# mother.net
KiCad netlist of a schematic drawn in EAGLE
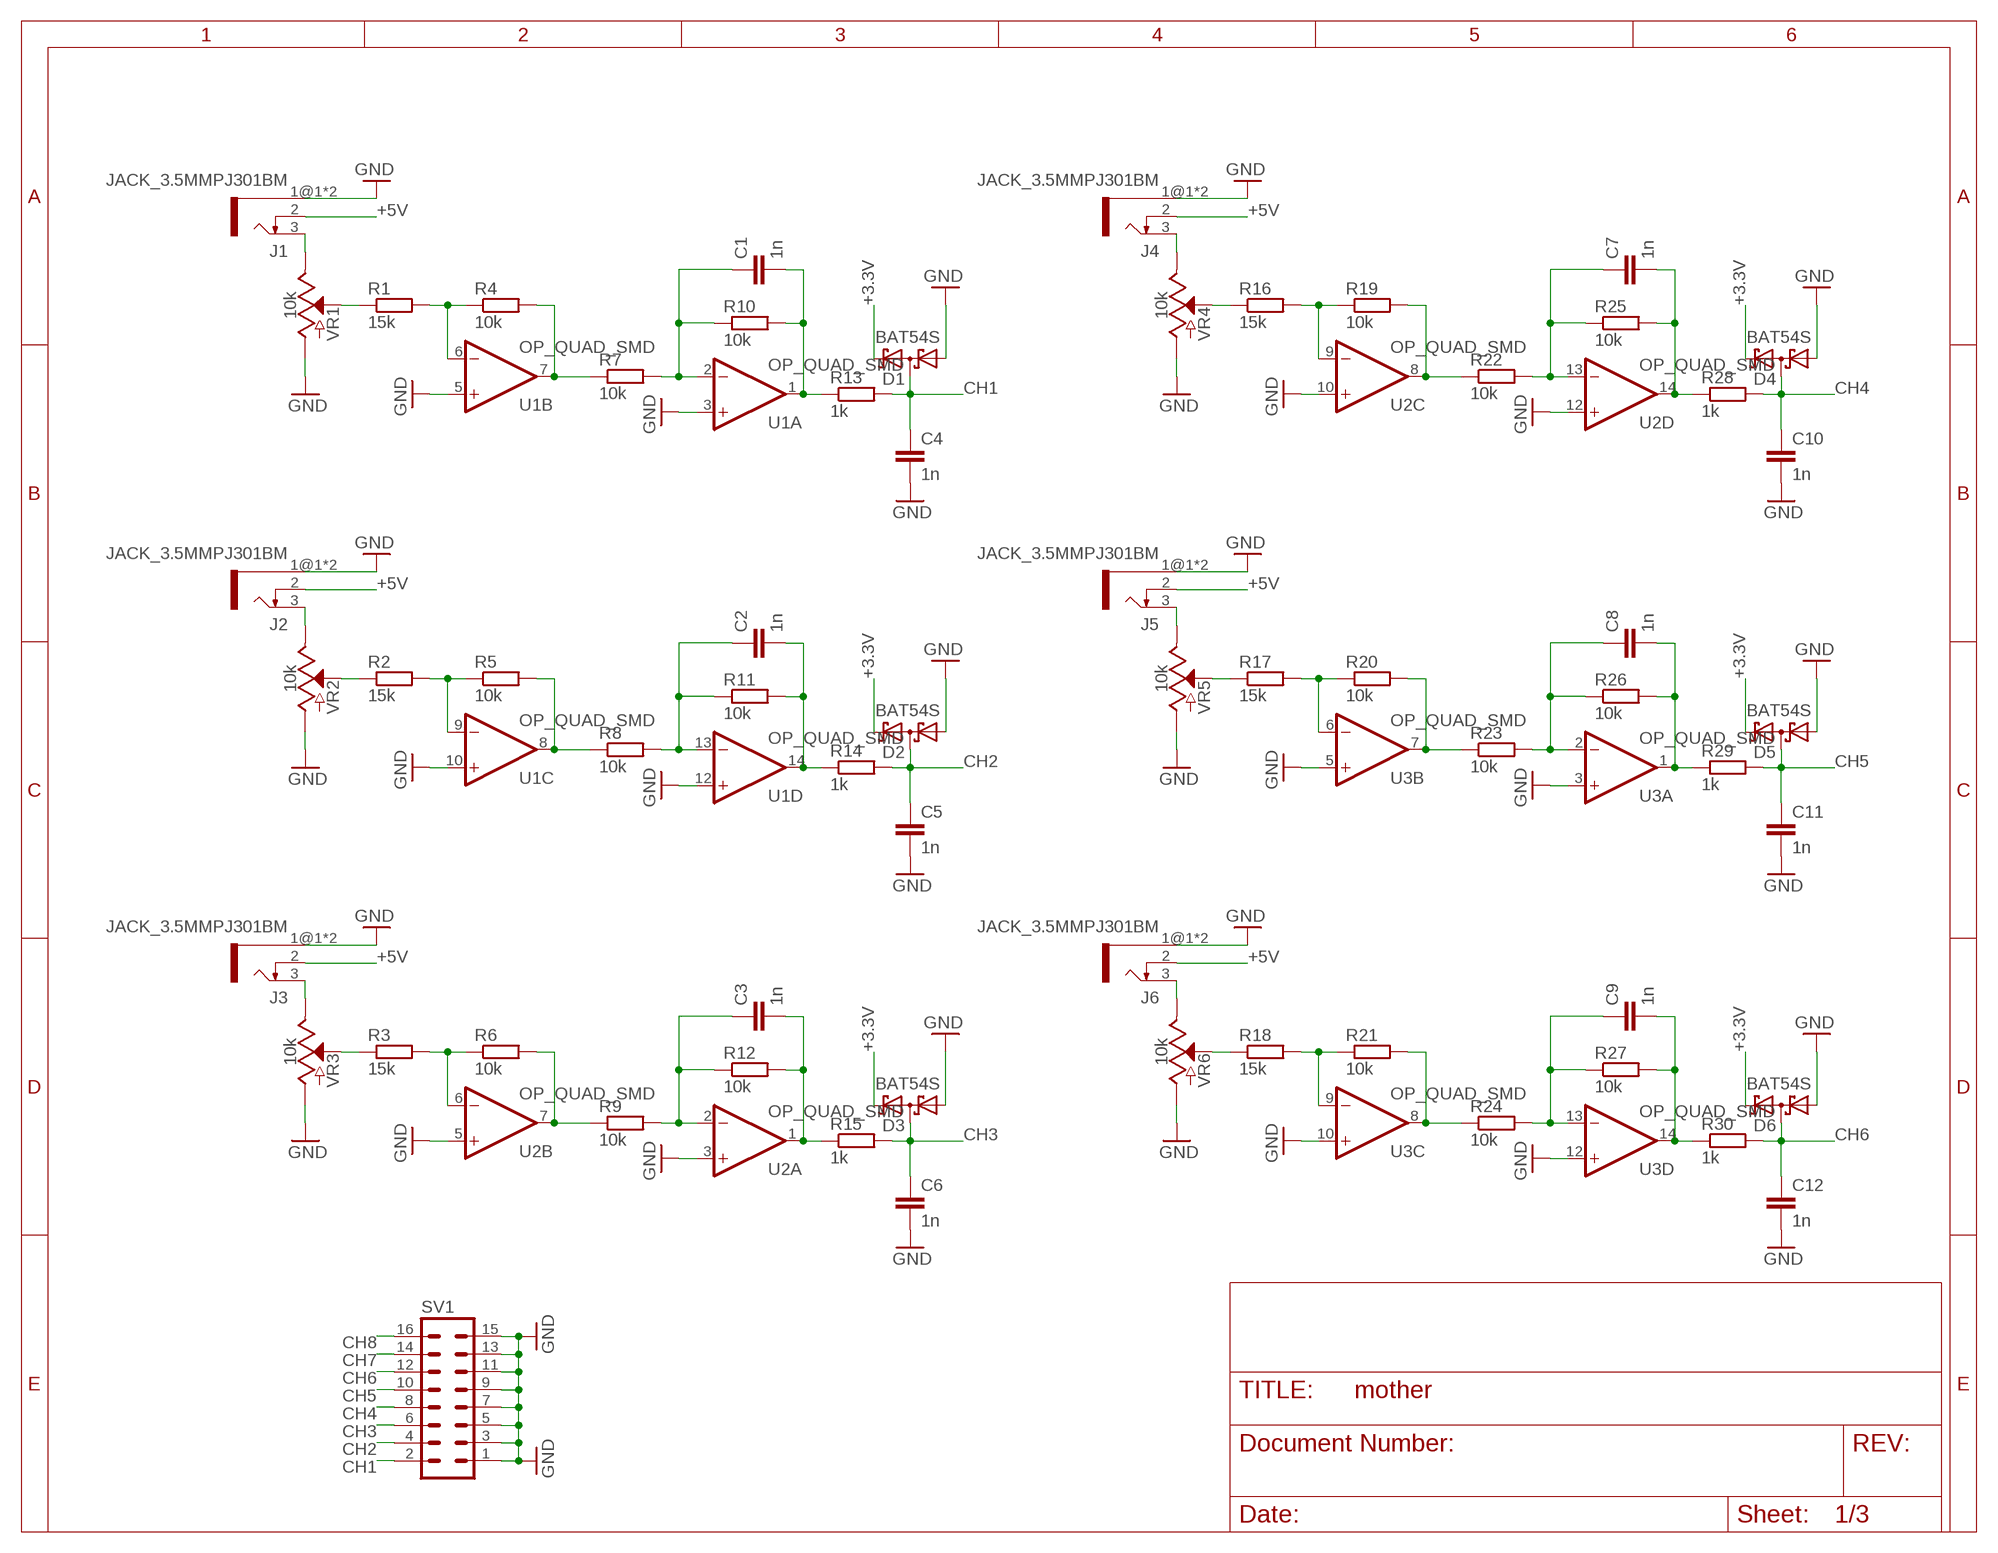
[diagram p0: schematic, sheet 1]
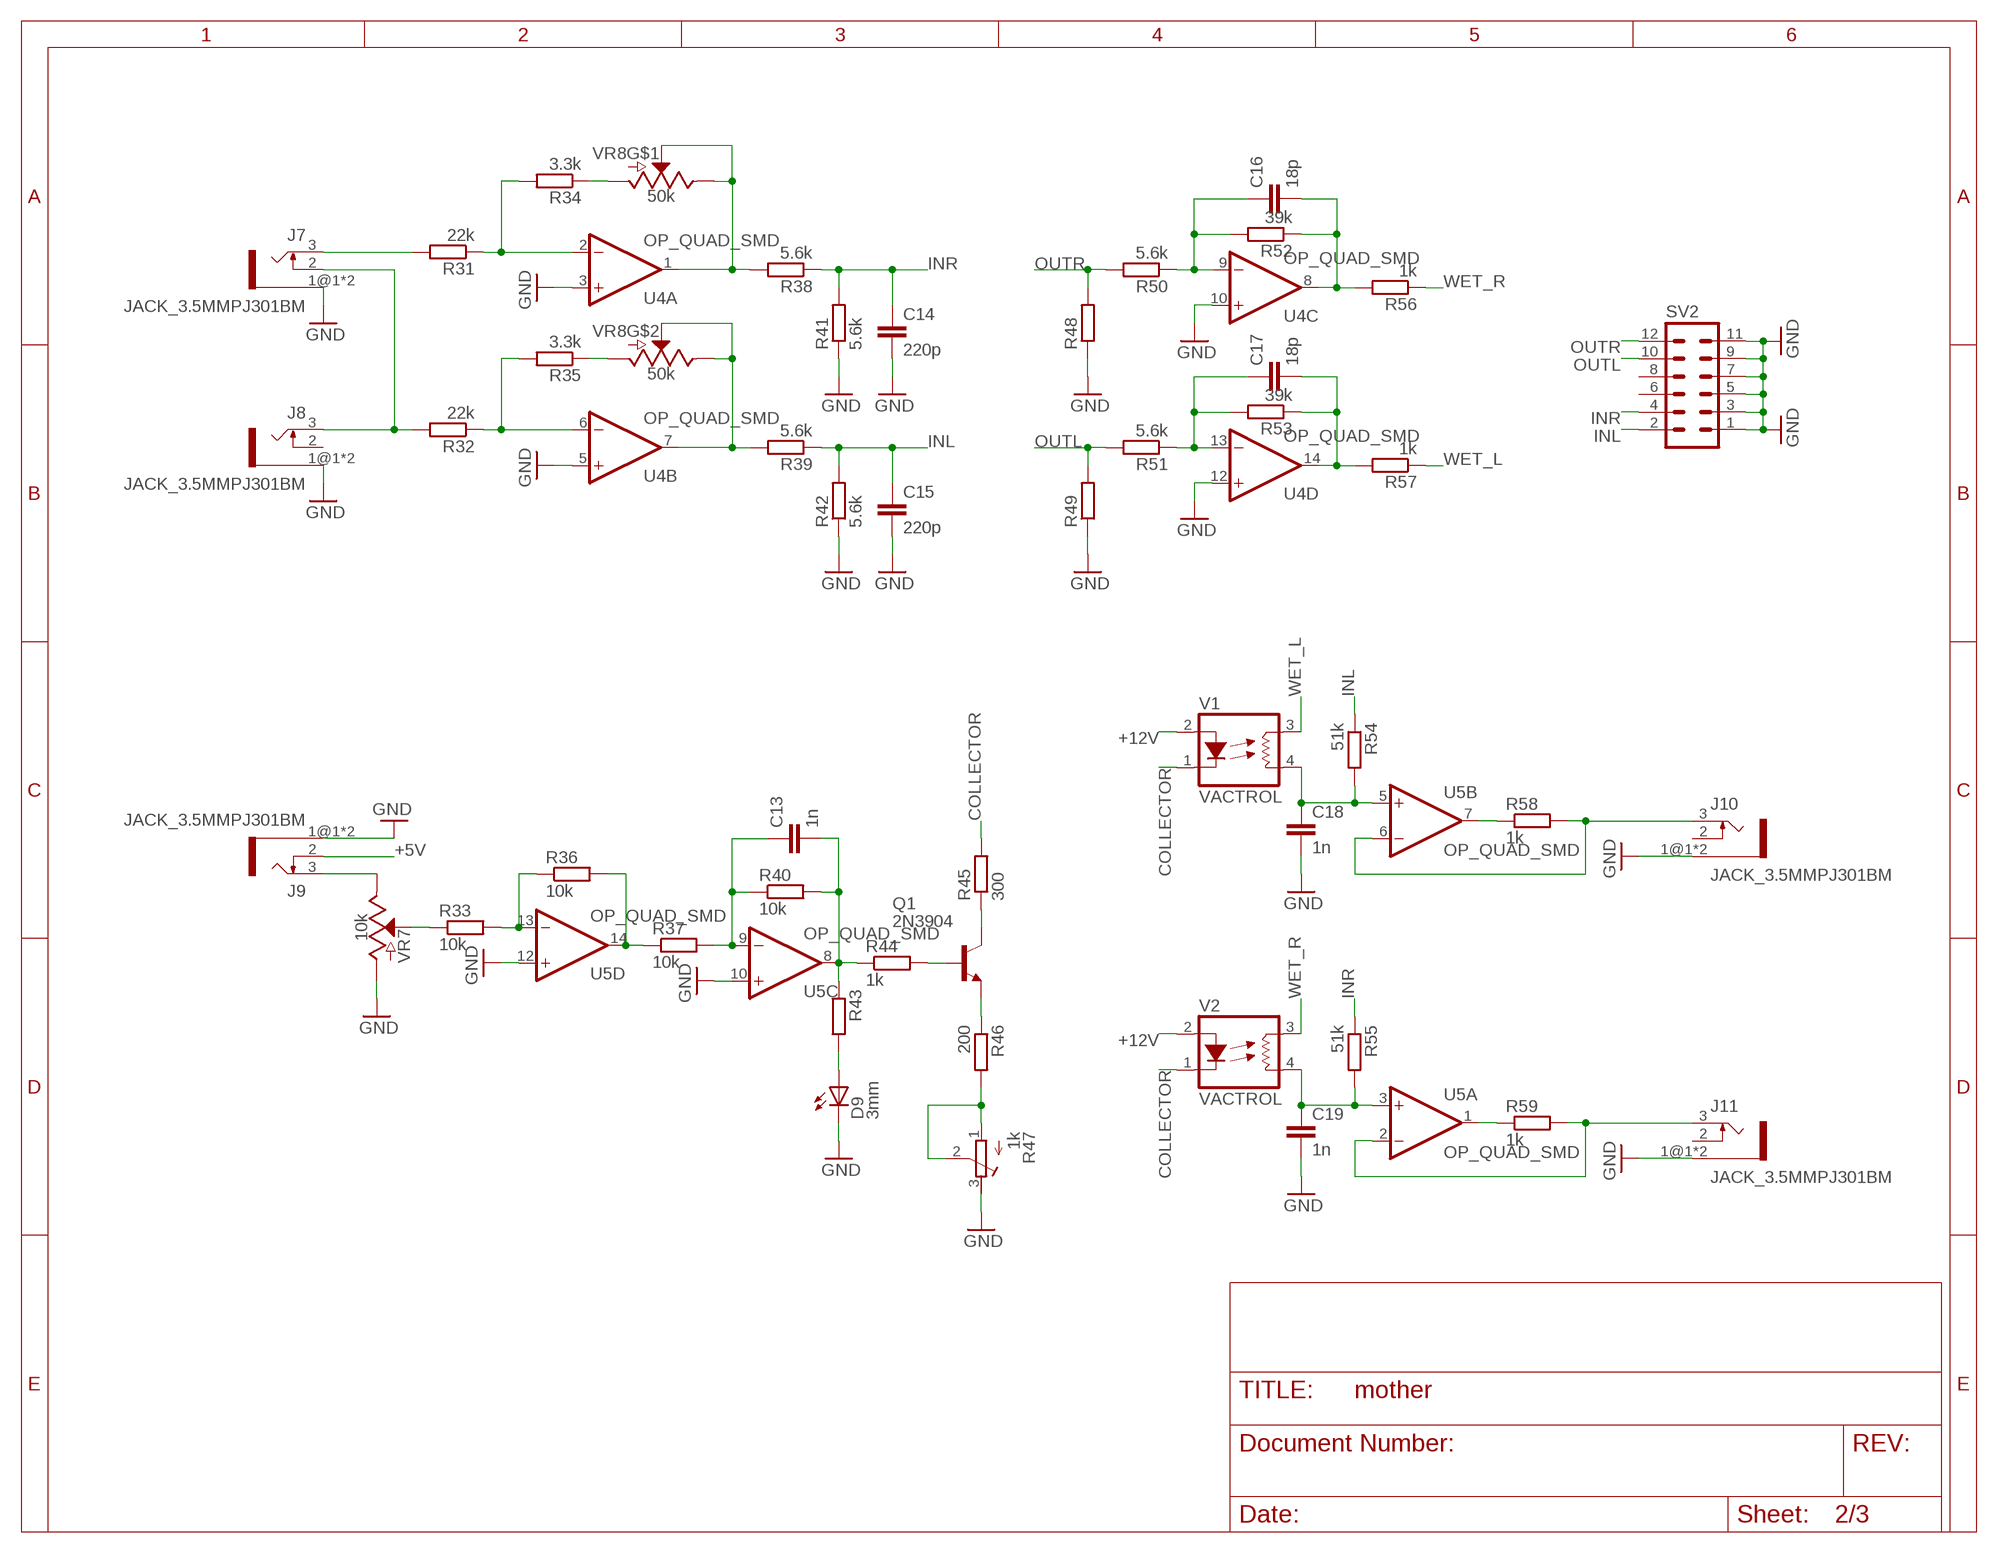
[diagram p1: schematic, sheet 2]
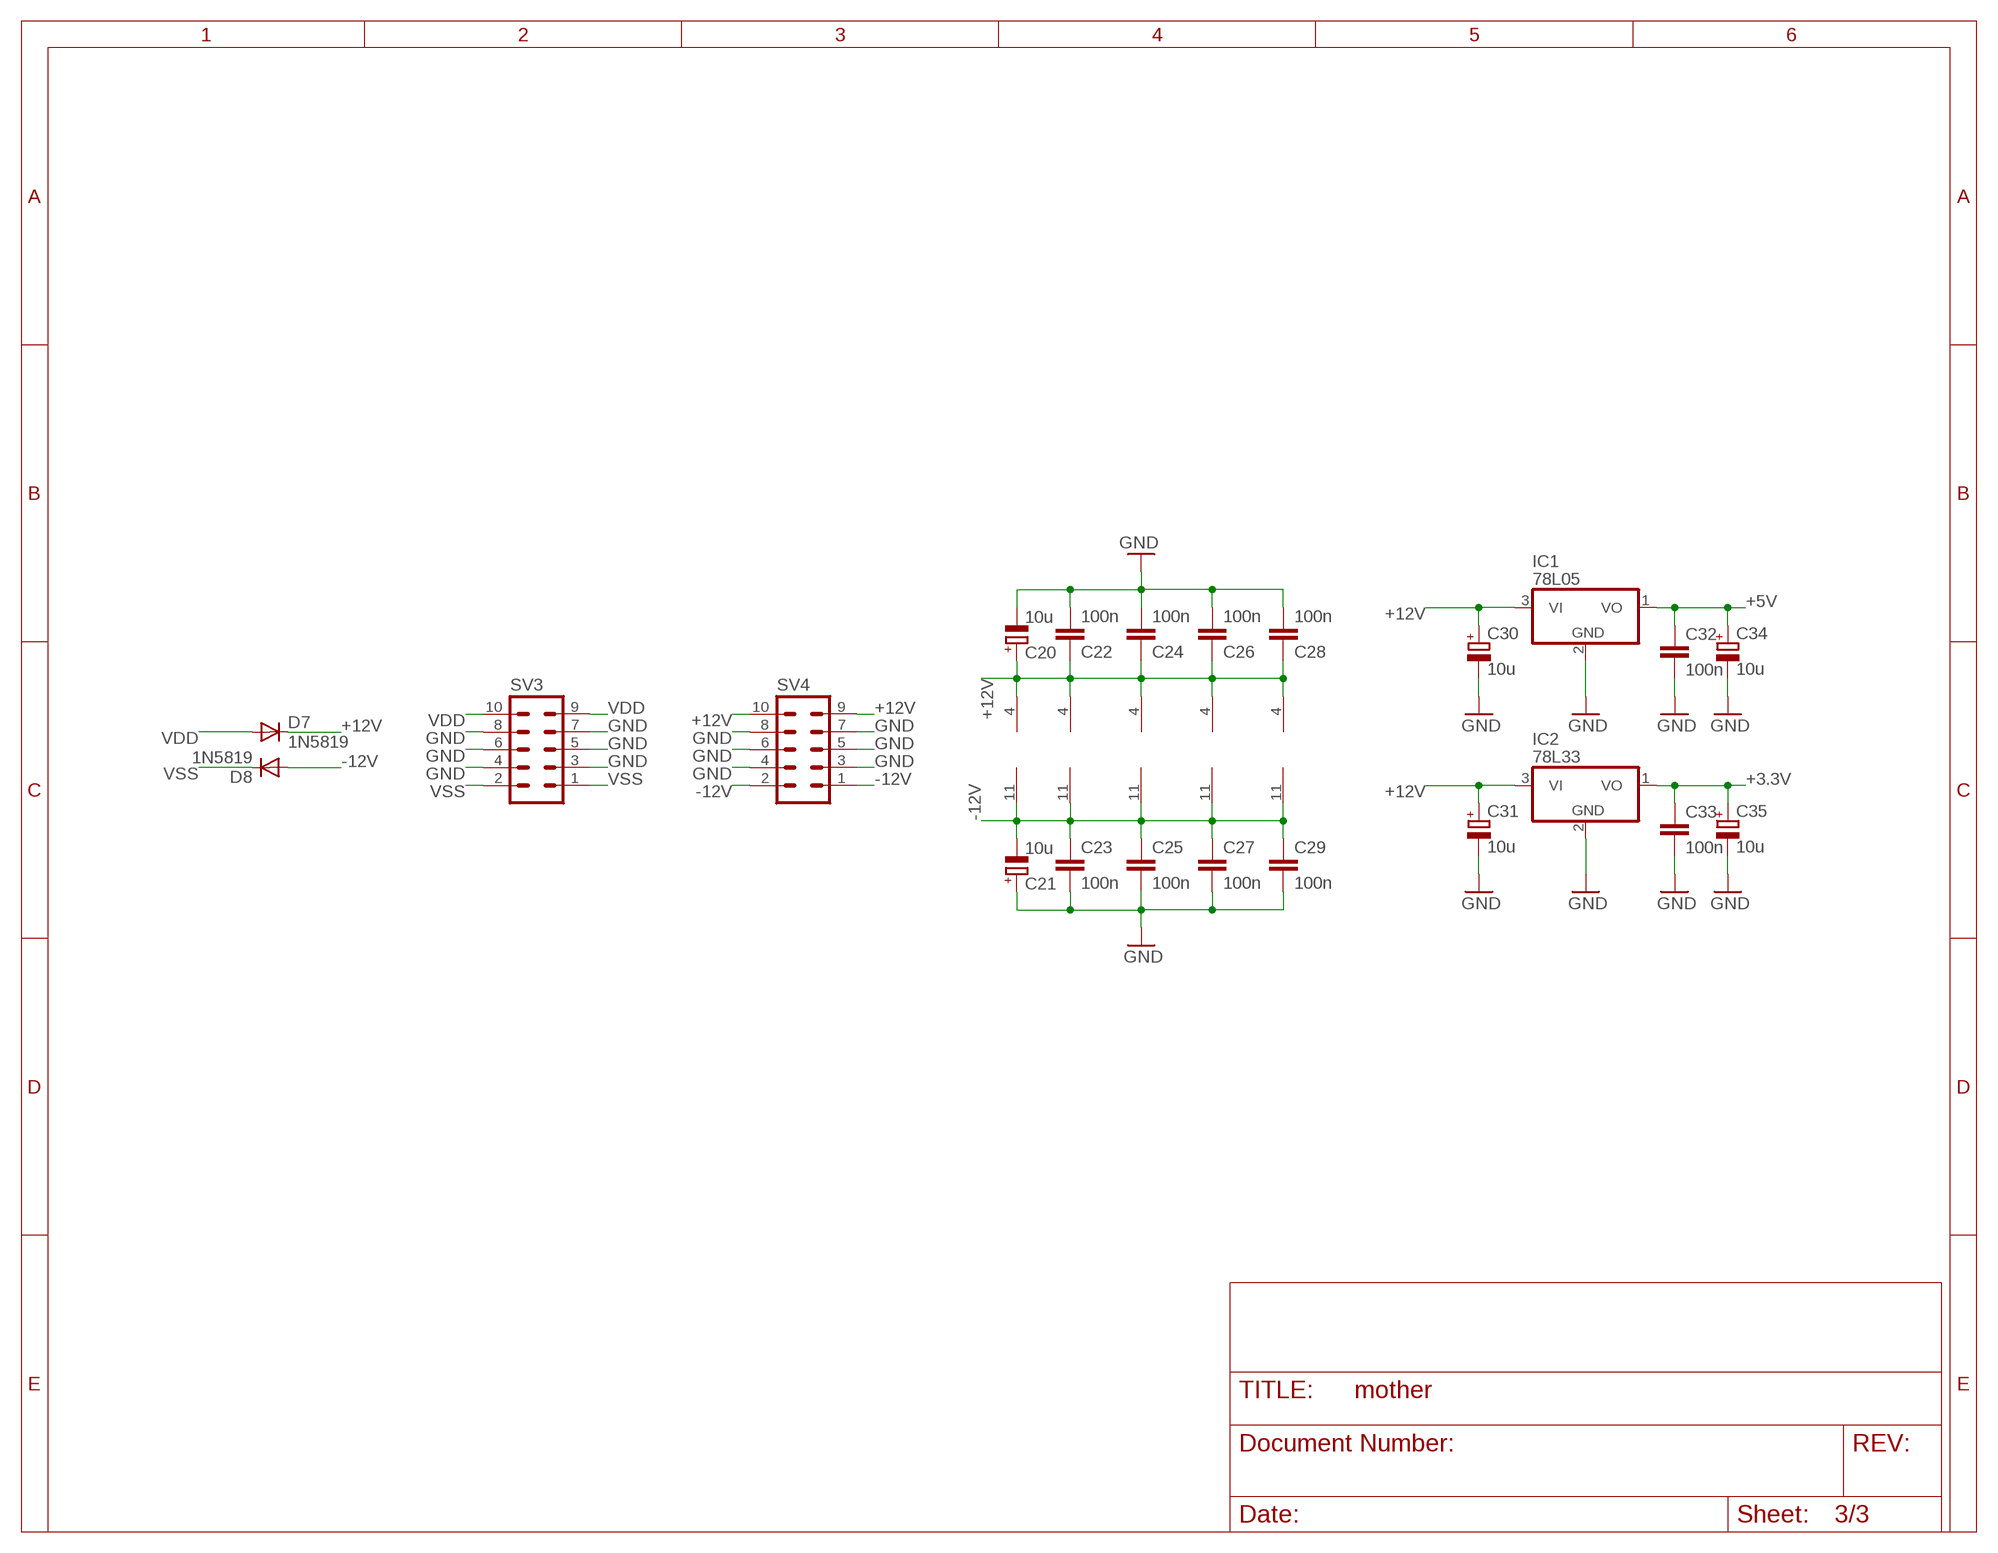
[diagram p2: schematic, sheet 3]

(export (version "E")
  (design (tool "Eeschema 10.0.6"))
  (components
    (comp (ref "C20")
      (value "10u")
      (footprint "eagle-import:E2,5-6")
      (libsource (lib "eagle-import") (part "CPOL-EUE2.5-6"))
    )
    (comp (ref "C21")
      (value "10u")
      (footprint "eagle-import:E2,5-6")
      (libsource (lib "eagle-import") (part "CPOL-EUE2.5-6"))
    )
    (comp (ref "C22")
      (value "100n")
      (footprint "eagle-import:C5B3.5")
      (libsource (lib "eagle-import") (part "C5/3.5"))
    )
    (comp (ref "C23")
      (value "100n")
      (footprint "eagle-import:C5B3.5")
      (libsource (lib "eagle-import") (part "C5/3.5"))
    )
    (comp (ref "C24")
      (value "100n")
      (footprint "eagle-import:C5B3.5")
      (libsource (lib "eagle-import") (part "C5/3.5"))
    )
    (comp (ref "C25")
      (value "100n")
      (footprint "eagle-import:C5B3.5")
      (libsource (lib "eagle-import") (part "C5/3.5"))
    )
    (comp (ref "C26")
      (value "100n")
      (footprint "eagle-import:C5B3.5")
      (libsource (lib "eagle-import") (part "C5/3.5"))
    )
    (comp (ref "C27")
      (value "100n")
      (footprint "eagle-import:C5B3.5")
      (libsource (lib "eagle-import") (part "C5/3.5"))
    )
    (comp (ref "C28")
      (value "100n")
      (footprint "eagle-import:C5B3.5")
      (libsource (lib "eagle-import") (part "C5/3.5"))
    )
    (comp (ref "C29")
      (value "100n")
      (footprint "eagle-import:C5B3.5")
      (libsource (lib "eagle-import") (part "C5/3.5"))
    )
    (comp (ref "C30")
      (value "10u")
      (footprint "eagle-import:E2,5-6")
      (libsource (lib "eagle-import") (part "CPOL-EUE2.5-6"))
    )
    (comp (ref "C31")
      (value "10u")
      (footprint "eagle-import:E2,5-6")
      (libsource (lib "eagle-import") (part "CPOL-EUE2.5-6"))
    )
    (comp (ref "C32")
      (value "100n")
      (footprint "eagle-import:C5B3.5")
      (libsource (lib "eagle-import") (part "C5/3.5"))
    )
    (comp (ref "C33")
      (value "100n")
      (footprint "eagle-import:C5B3.5")
      (libsource (lib "eagle-import") (part "C5/3.5"))
    )
    (comp (ref "C34")
      (value "10u")
      (footprint "eagle-import:E2,5-6")
      (libsource (lib "eagle-import") (part "CPOL-EUE2.5-6"))
    )
    (comp (ref "C35")
      (value "10u")
      (footprint "eagle-import:E2,5-6")
      (libsource (lib "eagle-import") (part "CPOL-EUE2.5-6"))
    )
    (comp (ref "D7")
      (value "1N5819")
      (footprint "eagle-import:SOD-123_MINI-SMA")
      (libsource (lib "eagle-import") (part "CGRM400-G1"))
    )
    (comp (ref "D8")
      (value "1N5819")
      (footprint "eagle-import:SOD-123_MINI-SMA")
      (libsource (lib "eagle-import") (part "CGRM400-G1"))
    )
    (comp (ref "IC1")
      (value "78L05")
      (footprint "eagle-import:TO92")
      (libsource (lib "eagle-import") (part "78ZL05"))
    )
    (comp (ref "IC2")
      (value "78L33")
      (footprint "eagle-import:TO92")
      (libsource (lib "eagle-import") (part "78ZL05"))
    )
    (comp (ref "SV3")
      (value "MA05-2")
      (footprint "eagle-import:MA05-2")
      (libsource (lib "eagle-import") (part "MA05-2"))
    )
    (comp (ref "SV4")
      (value "MA05-2")
      (footprint "eagle-import:MA05-2")
      (libsource (lib "eagle-import") (part "MA05-2"))
    )
    (comp (ref "U1")
      (value "OP_QUAD_SMD")
      (footprint "eagle-import:SO14")
      (libsource (lib "eagle-import") (part "OP_QUAD_SMD"))
    )
    (comp (ref "U2")
      (value "OP_QUAD_SMD")
      (footprint "eagle-import:SO14")
      (libsource (lib "eagle-import") (part "OP_QUAD_SMD"))
    )
    (comp (ref "U3")
      (value "OP_QUAD_SMD")
      (footprint "eagle-import:SO14")
      (libsource (lib "eagle-import") (part "OP_QUAD_SMD"))
    )
    (comp (ref "U4")
      (value "OP_QUAD_SMD")
      (footprint "eagle-import:SO14")
      (libsource (lib "eagle-import") (part "OP_QUAD_SMD"))
    )
    (comp (ref "U5")
      (value "OP_QUAD_SMD")
      (footprint "eagle-import:SO14")
      (libsource (lib "eagle-import") (part "OP_QUAD_SMD"))
    )
    (comp (ref "C1")
      (value "1n")
      (footprint "eagle-import:C0603")
      (libsource (lib "eagle-import") (part "CC0603"))
    )
    (comp (ref "C2")
      (value "1n")
      (footprint "eagle-import:C0603")
      (libsource (lib "eagle-import") (part "CC0603"))
    )
    (comp (ref "C3")
      (value "1n")
      (footprint "eagle-import:C0603")
      (libsource (lib "eagle-import") (part "CC0603"))
    )
    (comp (ref "C4")
      (value "1n")
      (footprint "eagle-import:C0603")
      (libsource (lib "eagle-import") (part "CC0603"))
    )
    (comp (ref "C5")
      (value "1n")
      (footprint "eagle-import:C0603")
      (libsource (lib "eagle-import") (part "CC0603"))
    )
    (comp (ref "C6")
      (value "1n")
      (footprint "eagle-import:C0603")
      (libsource (lib "eagle-import") (part "CC0603"))
    )
    (comp (ref "C7")
      (value "1n")
      (footprint "eagle-import:C0603")
      (libsource (lib "eagle-import") (part "CC0603"))
    )
    (comp (ref "C8")
      (value "1n")
      (footprint "eagle-import:C0603")
      (libsource (lib "eagle-import") (part "CC0603"))
    )
    (comp (ref "C9")
      (value "1n")
      (footprint "eagle-import:C0603")
      (libsource (lib "eagle-import") (part "CC0603"))
    )
    (comp (ref "C10")
      (value "1n")
      (footprint "eagle-import:C0603")
      (libsource (lib "eagle-import") (part "CC0603"))
    )
    (comp (ref "C11")
      (value "1n")
      (footprint "eagle-import:C0603")
      (libsource (lib "eagle-import") (part "CC0603"))
    )
    (comp (ref "C12")
      (value "1n")
      (footprint "eagle-import:C0603")
      (libsource (lib "eagle-import") (part "CC0603"))
    )
    (comp (ref "D1")
      (value "BAT54S")
      (footprint "eagle-import:SOT23")
      (libsource (lib "eagle-import") (part "BAT54S"))
    )
    (comp (ref "D2")
      (value "BAT54S")
      (footprint "eagle-import:SOT23")
      (libsource (lib "eagle-import") (part "BAT54S"))
    )
    (comp (ref "D3")
      (value "BAT54S")
      (footprint "eagle-import:SOT23")
      (libsource (lib "eagle-import") (part "BAT54S"))
    )
    (comp (ref "D4")
      (value "BAT54S")
      (footprint "eagle-import:SOT23")
      (libsource (lib "eagle-import") (part "BAT54S"))
    )
    (comp (ref "D5")
      (value "BAT54S")
      (footprint "eagle-import:SOT23")
      (libsource (lib "eagle-import") (part "BAT54S"))
    )
    (comp (ref "D6")
      (value "BAT54S")
      (footprint "eagle-import:SOT23")
      (libsource (lib "eagle-import") (part "BAT54S"))
    )
    (comp (ref "J1")
      (value "JACK_3.5MMPJ301BM")
      (footprint "eagle-import:PJ301BM_JACK")
      (libsource (lib "eagle-import") (part "JACK_3.5MMPJ301BM"))
    )
    (comp (ref "J2")
      (value "JACK_3.5MMPJ301BM")
      (footprint "eagle-import:PJ301BM_JACK")
      (libsource (lib "eagle-import") (part "JACK_3.5MMPJ301BM"))
    )
    (comp (ref "J3")
      (value "JACK_3.5MMPJ301BM")
      (footprint "eagle-import:PJ301BM_JACK")
      (libsource (lib "eagle-import") (part "JACK_3.5MMPJ301BM"))
    )
    (comp (ref "J4")
      (value "JACK_3.5MMPJ301BM")
      (footprint "eagle-import:PJ301BM_JACK")
      (libsource (lib "eagle-import") (part "JACK_3.5MMPJ301BM"))
    )
    (comp (ref "J5")
      (value "JACK_3.5MMPJ301BM")
      (footprint "eagle-import:PJ301BM_JACK")
      (libsource (lib "eagle-import") (part "JACK_3.5MMPJ301BM"))
    )
    (comp (ref "J6")
      (value "JACK_3.5MMPJ301BM")
      (footprint "eagle-import:PJ301BM_JACK")
      (libsource (lib "eagle-import") (part "JACK_3.5MMPJ301BM"))
    )
    (comp (ref "R1")
      (value "15k")
      (footprint "eagle-import:R0603")
      (libsource (lib "eagle-import") (part "RR0603"))
    )
    (comp (ref "R2")
      (value "15k")
      (footprint "eagle-import:R0603")
      (libsource (lib "eagle-import") (part "RR0603"))
    )
    (comp (ref "R3")
      (value "15k")
      (footprint "eagle-import:R0603")
      (libsource (lib "eagle-import") (part "RR0603"))
    )
    (comp (ref "R4")
      (value "10k")
      (footprint "eagle-import:R0603")
      (libsource (lib "eagle-import") (part "RR0603"))
    )
    (comp (ref "R5")
      (value "10k")
      (footprint "eagle-import:R0603")
      (libsource (lib "eagle-import") (part "RR0603"))
    )
    (comp (ref "R6")
      (value "10k")
      (footprint "eagle-import:R0603")
      (libsource (lib "eagle-import") (part "RR0603"))
    )
    (comp (ref "R7")
      (value "10k")
      (footprint "eagle-import:R0603")
      (libsource (lib "eagle-import") (part "RR0603"))
    )
    (comp (ref "R8")
      (value "10k")
      (footprint "eagle-import:R0603")
      (libsource (lib "eagle-import") (part "RR0603"))
    )
    (comp (ref "R9")
      (value "10k")
      (footprint "eagle-import:R0603")
      (libsource (lib "eagle-import") (part "RR0603"))
    )
    (comp (ref "R10")
      (value "10k")
      (footprint "eagle-import:R0603")
      (libsource (lib "eagle-import") (part "RR0603"))
    )
    (comp (ref "R11")
      (value "10k")
      (footprint "eagle-import:R0603")
      (libsource (lib "eagle-import") (part "RR0603"))
    )
    (comp (ref "R12")
      (value "10k")
      (footprint "eagle-import:R0603")
      (libsource (lib "eagle-import") (part "RR0603"))
    )
    (comp (ref "R13")
      (value "1k")
      (footprint "eagle-import:R0603")
      (libsource (lib "eagle-import") (part "RR0603"))
    )
    (comp (ref "R14")
      (value "1k")
      (footprint "eagle-import:R0603")
      (libsource (lib "eagle-import") (part "RR0603"))
    )
    (comp (ref "R15")
      (value "1k")
      (footprint "eagle-import:R0603")
      (libsource (lib "eagle-import") (part "RR0603"))
    )
    (comp (ref "R16")
      (value "15k")
      (footprint "eagle-import:R0603")
      (libsource (lib "eagle-import") (part "RR0603"))
    )
    (comp (ref "R17")
      (value "15k")
      (footprint "eagle-import:R0603")
      (libsource (lib "eagle-import") (part "RR0603"))
    )
    (comp (ref "R18")
      (value "15k")
      (footprint "eagle-import:R0603")
      (libsource (lib "eagle-import") (part "RR0603"))
    )
    (comp (ref "R19")
      (value "10k")
      (footprint "eagle-import:R0603")
      (libsource (lib "eagle-import") (part "RR0603"))
    )
    (comp (ref "R20")
      (value "10k")
      (footprint "eagle-import:R0603")
      (libsource (lib "eagle-import") (part "RR0603"))
    )
    (comp (ref "R21")
      (value "10k")
      (footprint "eagle-import:R0603")
      (libsource (lib "eagle-import") (part "RR0603"))
    )
    (comp (ref "R22")
      (value "10k")
      (footprint "eagle-import:R0603")
      (libsource (lib "eagle-import") (part "RR0603"))
    )
    (comp (ref "R23")
      (value "10k")
      (footprint "eagle-import:R0603")
      (libsource (lib "eagle-import") (part "RR0603"))
    )
    (comp (ref "R24")
      (value "10k")
      (footprint "eagle-import:R0603")
      (libsource (lib "eagle-import") (part "RR0603"))
    )
    (comp (ref "R25")
      (value "10k")
      (footprint "eagle-import:R0603")
      (libsource (lib "eagle-import") (part "RR0603"))
    )
    (comp (ref "R26")
      (value "10k")
      (footprint "eagle-import:R0603")
      (libsource (lib "eagle-import") (part "RR0603"))
    )
    (comp (ref "R27")
      (value "10k")
      (footprint "eagle-import:R0603")
      (libsource (lib "eagle-import") (part "RR0603"))
    )
    (comp (ref "R28")
      (value "1k")
      (footprint "eagle-import:R0603")
      (libsource (lib "eagle-import") (part "RR0603"))
    )
    (comp (ref "R29")
      (value "1k")
      (footprint "eagle-import:R0603")
      (libsource (lib "eagle-import") (part "RR0603"))
    )
    (comp (ref "R30")
      (value "1k")
      (footprint "eagle-import:R0603")
      (libsource (lib "eagle-import") (part "RR0603"))
    )
    (comp (ref "SV1")
      (value "MA08-2")
      (footprint "eagle-import:MA08-2")
      (libsource (lib "eagle-import") (part "MA08-2"))
    )
    (comp (ref "VR1")
      (value "10k")
      (footprint "eagle-import:POT-PTH-ALPS-KIT")
      (libsource (lib "eagle-import") (part "POTENTIOMETER-PTH-9MM-1/20W-20%-KIT"))
    )
    (comp (ref "VR2")
      (value "10k")
      (footprint "eagle-import:POT-PTH-ALPS-KIT")
      (libsource (lib "eagle-import") (part "POTENTIOMETER-PTH-9MM-1/20W-20%-KIT"))
    )
    (comp (ref "VR3")
      (value "10k")
      (footprint "eagle-import:POT-PTH-ALPS-KIT")
      (libsource (lib "eagle-import") (part "POTENTIOMETER-PTH-9MM-1/20W-20%-KIT"))
    )
    (comp (ref "VR4")
      (value "10k")
      (footprint "eagle-import:POT-PTH-ALPS-KIT")
      (libsource (lib "eagle-import") (part "POTENTIOMETER-PTH-9MM-1/20W-20%-KIT"))
    )
    (comp (ref "VR5")
      (value "10k")
      (footprint "eagle-import:POT-PTH-ALPS-KIT")
      (libsource (lib "eagle-import") (part "POTENTIOMETER-PTH-9MM-1/20W-20%-KIT"))
    )
    (comp (ref "VR6")
      (value "10k")
      (footprint "eagle-import:POT-PTH-ALPS-KIT")
      (libsource (lib "eagle-import") (part "POTENTIOMETER-PTH-9MM-1/20W-20%-KIT"))
    )
    (comp (ref "C13")
      (value "1n")
      (footprint "eagle-import:C0603")
      (libsource (lib "eagle-import") (part "CC0603"))
    )
    (comp (ref "C14")
      (value "220p")
      (footprint "eagle-import:C0603")
      (libsource (lib "eagle-import") (part "CC0603"))
    )
    (comp (ref "C15")
      (value "220p")
      (footprint "eagle-import:C0603")
      (libsource (lib "eagle-import") (part "CC0603"))
    )
    (comp (ref "C16")
      (value "18p")
      (footprint "eagle-import:C0603")
      (libsource (lib "eagle-import") (part "CC0603"))
    )
    (comp (ref "C17")
      (value "18p")
      (footprint "eagle-import:C0603")
      (libsource (lib "eagle-import") (part "CC0603"))
    )
    (comp (ref "C18")
      (value "1n")
      (footprint "eagle-import:C0603")
      (libsource (lib "eagle-import") (part "CC0603"))
    )
    (comp (ref "C19")
      (value "1n")
      (footprint "eagle-import:C0603")
      (libsource (lib "eagle-import") (part "CC0603"))
    )
    (comp (ref "D9")
      (value "3mm")
      (footprint "eagle-import:LED3MM")
      (libsource (lib "eagle-import") (part "LED3MM"))
    )
    (comp (ref "J7")
      (value "JACK_3.5MMPJ301BM")
      (footprint "eagle-import:PJ301BM_JACK")
      (libsource (lib "eagle-import") (part "JACK_3.5MMPJ301BM"))
    )
    (comp (ref "J8")
      (value "JACK_3.5MMPJ301BM")
      (footprint "eagle-import:PJ301BM_JACK")
      (libsource (lib "eagle-import") (part "JACK_3.5MMPJ301BM"))
    )
    (comp (ref "J9")
      (value "JACK_3.5MMPJ301BM")
      (footprint "eagle-import:PJ301BM_JACK")
      (libsource (lib "eagle-import") (part "JACK_3.5MMPJ301BM"))
    )
    (comp (ref "J10")
      (value "JACK_3.5MMPJ301BM")
      (footprint "eagle-import:PJ301BM_JACK")
      (libsource (lib "eagle-import") (part "JACK_3.5MMPJ301BM"))
    )
    (comp (ref "J11")
      (value "JACK_3.5MMPJ301BM")
      (footprint "eagle-import:PJ301BM_JACK")
      (libsource (lib "eagle-import") (part "JACK_3.5MMPJ301BM"))
    )
    (comp (ref "Q1")
      (value "2N3904")
      (footprint "eagle-import:TO92")
      (libsource (lib "eagle-import") (part "2N3904"))
    )
    (comp (ref "R31")
      (value "22k")
      (footprint "eagle-import:R0603")
      (libsource (lib "eagle-import") (part "RR0603"))
    )
    (comp (ref "R32")
      (value "22k")
      (footprint "eagle-import:R0603")
      (libsource (lib "eagle-import") (part "RR0603"))
    )
    (comp (ref "R33")
      (value "10k")
      (footprint "eagle-import:R0603")
      (libsource (lib "eagle-import") (part "RR0603"))
    )
    (comp (ref "R34")
      (value "3.3k")
      (footprint "eagle-import:R0603")
      (libsource (lib "eagle-import") (part "RR0603"))
    )
    (comp (ref "R35")
      (value "3.3k")
      (footprint "eagle-import:R0603")
      (libsource (lib "eagle-import") (part "RR0603"))
    )
    (comp (ref "R36")
      (value "10k")
      (footprint "eagle-import:R0603")
      (libsource (lib "eagle-import") (part "RR0603"))
    )
    (comp (ref "R37")
      (value "10k")
      (footprint "eagle-import:R0603")
      (libsource (lib "eagle-import") (part "RR0603"))
    )
    (comp (ref "R38")
      (value "5.6k")
      (footprint "eagle-import:R0603")
      (libsource (lib "eagle-import") (part "RR0603"))
    )
    (comp (ref "R39")
      (value "5.6k")
      (footprint "eagle-import:R0603")
      (libsource (lib "eagle-import") (part "RR0603"))
    )
    (comp (ref "R40")
      (value "10k")
      (footprint "eagle-import:R0603")
      (libsource (lib "eagle-import") (part "RR0603"))
    )
    (comp (ref "R41")
      (value "5.6k")
      (footprint "eagle-import:R0603")
      (libsource (lib "eagle-import") (part "RR0603"))
    )
    (comp (ref "R42")
      (value "5.6k")
      (footprint "eagle-import:R0603")
      (libsource (lib "eagle-import") (part "RR0603"))
    )
    (comp (ref "R43")
      (value "RESISTOR10MM")
      (footprint "eagle-import:1_4W_RESISTOR")
      (libsource (lib "eagle-import") (part "RESISTOR10MM"))
    )
    (comp (ref "R44")
      (value "1k")
      (footprint "eagle-import:R0603")
      (libsource (lib "eagle-import") (part "RR0603"))
    )
    (comp (ref "R45")
      (value "300")
      (footprint "eagle-import:1_4W_RESISTOR")
      (libsource (lib "eagle-import") (part "RESISTOR10MM"))
    )
    (comp (ref "R46")
      (value "200")
      (footprint "eagle-import:R0603")
      (libsource (lib "eagle-import") (part "RR0603"))
    )
    (comp (ref "R47")
      (value "1k")
      (footprint "eagle-import:RTRIM64W")
      (libsource (lib "eagle-import") (part "R-TRIMM64W"))
    )
    (comp (ref "R48")
      (value "RR0603")
      (footprint "eagle-import:R0603")
      (libsource (lib "eagle-import") (part "RR0603"))
    )
    (comp (ref "R49")
      (value "RR0603")
      (footprint "eagle-import:R0603")
      (libsource (lib "eagle-import") (part "RR0603"))
    )
    (comp (ref "R50")
      (value "5.6k")
      (footprint "eagle-import:R0603")
      (libsource (lib "eagle-import") (part "RR0603"))
    )
    (comp (ref "R51")
      (value "5.6k")
      (footprint "eagle-import:R0603")
      (libsource (lib "eagle-import") (part "RR0603"))
    )
    (comp (ref "R52")
      (value "39k")
      (footprint "eagle-import:R0603")
      (libsource (lib "eagle-import") (part "RR0603"))
    )
    (comp (ref "R53")
      (value "39k")
      (footprint "eagle-import:R0603")
      (libsource (lib "eagle-import") (part "RR0603"))
    )
    (comp (ref "R54")
      (value "51k")
      (footprint "eagle-import:R0603")
      (libsource (lib "eagle-import") (part "RR0603"))
    )
    (comp (ref "R55")
      (value "51k")
      (footprint "eagle-import:R0603")
      (libsource (lib "eagle-import") (part "RR0603"))
    )
    (comp (ref "R56")
      (value "1k")
      (footprint "eagle-import:R0603")
      (libsource (lib "eagle-import") (part "RR0603"))
    )
    (comp (ref "R57")
      (value "1k")
      (footprint "eagle-import:R0603")
      (libsource (lib "eagle-import") (part "RR0603"))
    )
    (comp (ref "R58")
      (value "1k")
      (footprint "eagle-import:R0603")
      (libsource (lib "eagle-import") (part "RR0603"))
    )
    (comp (ref "R59")
      (value "1k")
      (footprint "eagle-import:R0603")
      (libsource (lib "eagle-import") (part "RR0603"))
    )
    (comp (ref "SV2")
      (value "MA06-2")
      (footprint "eagle-import:MA06-2")
      (libsource (lib "eagle-import") (part "MA06-2"))
    )
    (comp (ref "V1")
      (value "VACTROL")
      (footprint "eagle-import:VACTROL_4PIN_VTL5C")
      (libsource (lib "eagle-import") (part "VACTROL"))
    )
    (comp (ref "V2")
      (value "VACTROL")
      (footprint "eagle-import:VACTROL_4PIN_VTL5C")
      (libsource (lib "eagle-import") (part "VACTROL"))
    )
    (comp (ref "VR7")
      (value "10k")
      (footprint "eagle-import:POT-PTH-ALPS-KIT")
      (libsource (lib "eagle-import") (part "POTENTIOMETER-PTH-9MM-1/20W-20%-KIT"))
    )
    (comp (ref "VR8")
      (value "50k")
      (footprint "eagle-import:POT-DUAL-PTH-PANASONIC-VERT-KIT")
      (libsource (lib "eagle-import") (part "POTENTIOMETER_DUAL-PTH-12MM-1/20W-20%-KIT"))
    )
  )
  (nets
    (net (code "1") (name "+3.3V") (class "Default")
      (node (ref "C33") (pin "1") (pinfunction "1_1") (pintype "passive"))
      (node (ref "C35") (pin "+") (pinfunction "+_+") (pintype "passive"))
      (node (ref "D1") (pin "2") (pinfunction "C2_2") (pintype "passive"))
      (node (ref "D2") (pin "2") (pinfunction "C2_2") (pintype "passive"))
      (node (ref "D3") (pin "2") (pinfunction "C2_2") (pintype "passive"))
      (node (ref "D4") (pin "2") (pinfunction "C2_2") (pintype "passive"))
      (node (ref "D5") (pin "2") (pinfunction "C2_2") (pintype "passive"))
      (node (ref "D6") (pin "2") (pinfunction "C2_2") (pintype "passive"))
      (node (ref "IC2") (pin "1") (pinfunction "VO_1") (pintype "passive"))
    )
    (net (code "2") (name "+5V") (class "Default")
      (node (ref "C32") (pin "1") (pinfunction "1_1") (pintype "passive"))
      (node (ref "C34") (pin "+") (pinfunction "+_+") (pintype "passive"))
      (node (ref "IC1") (pin "1") (pinfunction "VO_1") (pintype "passive"))
      (node (ref "J1") (pin "2") (pinfunction "2_2") (pintype "passive"))
      (node (ref "J2") (pin "2") (pinfunction "2_2") (pintype "passive"))
      (node (ref "J3") (pin "2") (pinfunction "2_2") (pintype "passive"))
      (node (ref "J4") (pin "2") (pinfunction "2_2") (pintype "passive"))
      (node (ref "J5") (pin "2") (pinfunction "2_2") (pintype "passive"))
      (node (ref "J6") (pin "2") (pinfunction "2_2") (pintype "passive"))
      (node (ref "J9") (pin "2") (pinfunction "2_2") (pintype "passive"))
    )
    (net (code "3") (name "+12V") (class "Default")
      (node (ref "C20") (pin "+") (pinfunction "+_+") (pintype "passive"))
      (node (ref "C22") (pin "1") (pinfunction "1_1") (pintype "passive"))
      (node (ref "C24") (pin "1") (pinfunction "1_1") (pintype "passive"))
      (node (ref "C26") (pin "1") (pinfunction "1_1") (pintype "passive"))
      (node (ref "C28") (pin "1") (pinfunction "1_1") (pintype "passive"))
      (node (ref "C30") (pin "+") (pinfunction "+_+") (pintype "passive"))
      (node (ref "C31") (pin "+") (pinfunction "+_+") (pintype "passive"))
      (node (ref "D7") (pin "C") (pinfunction "C_C") (pintype "passive"))
      (node (ref "IC1") (pin "3") (pinfunction "VI_3") (pintype "input"))
      (node (ref "IC2") (pin "3") (pinfunction "VI_3") (pintype "input"))
      (node (ref "SV4") (pin "10") (pinfunction "10_10") (pintype "passive"))
      (node (ref "SV4") (pin "9") (pinfunction "9_9") (pintype "passive"))
      (node (ref "U1") (pin "4") (pinfunction "V+_4") (pintype "power_in"))
      (node (ref "U2") (pin "4") (pinfunction "V+_4") (pintype "power_in"))
      (node (ref "U3") (pin "4") (pinfunction "V+_4") (pintype "power_in"))
      (node (ref "U4") (pin "4") (pinfunction "V+_4") (pintype "power_in"))
      (node (ref "U5") (pin "4") (pinfunction "V+_4") (pintype "power_in"))
      (node (ref "V1") (pin "2") (pinfunction "LED+_2") (pintype "passive"))
      (node (ref "V2") (pin "2") (pinfunction "LED+_2") (pintype "passive"))
    )
    (net (code "4") (name "-12V") (class "Default")
      (node (ref "C21") (pin "-") (pinfunction "-_-") (pintype "passive"))
      (node (ref "C23") (pin "1") (pinfunction "1_1") (pintype "passive"))
      (node (ref "C25") (pin "1") (pinfunction "1_1") (pintype "passive"))
      (node (ref "C27") (pin "1") (pinfunction "1_1") (pintype "passive"))
      (node (ref "C29") (pin "1") (pinfunction "1_1") (pintype "passive"))
      (node (ref "D8") (pin "A") (pinfunction "A_A") (pintype "passive"))
      (node (ref "SV4") (pin "1") (pinfunction "1_1") (pintype "passive"))
      (node (ref "SV4") (pin "2") (pinfunction "2_2") (pintype "passive"))
      (node (ref "U1") (pin "11") (pinfunction "V-_11") (pintype "power_in"))
      (node (ref "U2") (pin "11") (pinfunction "V-_11") (pintype "power_in"))
      (node (ref "U3") (pin "11") (pinfunction "V-_11") (pintype "power_in"))
      (node (ref "U4") (pin "11") (pinfunction "V-_11") (pintype "power_in"))
      (node (ref "U5") (pin "11") (pinfunction "V-_11") (pintype "power_in"))
    )
    (net (code "5") (name "CH1") (class "Default")
      (node (ref "C4") (pin "1") (pinfunction "1_1") (pintype "passive"))
      (node (ref "D1") (pin "3") (pinfunction "C1A2_3") (pintype "passive"))
      (node (ref "R13") (pin "2") (pinfunction "2_2") (pintype "passive"))
      (node (ref "SV1") (pin "2") (pinfunction "2_2") (pintype "passive"))
    )
    (net (code "6") (name "CH2") (class "Default")
      (node (ref "C5") (pin "1") (pinfunction "1_1") (pintype "passive"))
      (node (ref "D2") (pin "3") (pinfunction "C1A2_3") (pintype "passive"))
      (node (ref "R14") (pin "2") (pinfunction "2_2") (pintype "passive"))
      (node (ref "SV1") (pin "4") (pinfunction "4_4") (pintype "passive"))
    )
    (net (code "7") (name "CH3") (class "Default")
      (node (ref "C6") (pin "1") (pinfunction "1_1") (pintype "passive"))
      (node (ref "D3") (pin "3") (pinfunction "C1A2_3") (pintype "passive"))
      (node (ref "R15") (pin "2") (pinfunction "2_2") (pintype "passive"))
      (node (ref "SV1") (pin "6") (pinfunction "6_6") (pintype "passive"))
    )
    (net (code "8") (name "CH4") (class "Default")
      (node (ref "C10") (pin "1") (pinfunction "1_1") (pintype "passive"))
      (node (ref "D4") (pin "3") (pinfunction "C1A2_3") (pintype "passive"))
      (node (ref "R28") (pin "2") (pinfunction "2_2") (pintype "passive"))
      (node (ref "SV1") (pin "8") (pinfunction "8_8") (pintype "passive"))
    )
    (net (code "9") (name "CH5") (class "Default")
      (node (ref "C11") (pin "1") (pinfunction "1_1") (pintype "passive"))
      (node (ref "D5") (pin "3") (pinfunction "C1A2_3") (pintype "passive"))
      (node (ref "R29") (pin "2") (pinfunction "2_2") (pintype "passive"))
      (node (ref "SV1") (pin "10") (pinfunction "10_10") (pintype "passive"))
    )
    (net (code "10") (name "CH6") (class "Default")
      (node (ref "C12") (pin "1") (pinfunction "1_1") (pintype "passive"))
      (node (ref "D6") (pin "3") (pinfunction "C1A2_3") (pintype "passive"))
      (node (ref "R30") (pin "2") (pinfunction "2_2") (pintype "passive"))
      (node (ref "SV1") (pin "12") (pinfunction "12_12") (pintype "passive"))
    )
    (net (code "11") (name "CH7") (class "Default")
      (node (ref "SV1") (pin "14") (pinfunction "14_14") (pintype "passive"))
    )
    (net (code "12") (name "CH8") (class "Default")
      (node (ref "SV1") (pin "16") (pinfunction "16_16") (pintype "passive"))
    )
    (net (code "13") (name "COLLECTOR") (class "Default")
      (node (ref "R45") (pin "2") (pinfunction "2_2") (pintype "passive"))
      (node (ref "V1") (pin "1") (pinfunction "LED-_1") (pintype "passive"))
      (node (ref "V2") (pin "1") (pinfunction "LED-_1") (pintype "passive"))
    )
    (net (code "14") (name "GND") (class "Default")
      (node (ref "C10") (pin "2") (pinfunction "2_2") (pintype "passive"))
      (node (ref "C11") (pin "2") (pinfunction "2_2") (pintype "passive"))
      (node (ref "C12") (pin "2") (pinfunction "2_2") (pintype "passive"))
      (node (ref "C14") (pin "2") (pinfunction "2_2") (pintype "passive"))
      (node (ref "C15") (pin "2") (pinfunction "2_2") (pintype "passive"))
      (node (ref "C18") (pin "2") (pinfunction "2_2") (pintype "passive"))
      (node (ref "C19") (pin "2") (pinfunction "2_2") (pintype "passive"))
      (node (ref "C20") (pin "-") (pinfunction "-_-") (pintype "passive"))
      (node (ref "C21") (pin "+") (pinfunction "+_+") (pintype "passive"))
      (node (ref "C22") (pin "2") (pinfunction "2_2") (pintype "passive"))
      (node (ref "C23") (pin "2") (pinfunction "2_2") (pintype "passive"))
      (node (ref "C24") (pin "2") (pinfunction "2_2") (pintype "passive"))
      (node (ref "C25") (pin "2") (pinfunction "2_2") (pintype "passive"))
      (node (ref "C26") (pin "2") (pinfunction "2_2") (pintype "passive"))
      (node (ref "C27") (pin "2") (pinfunction "2_2") (pintype "passive"))
      (node (ref "C28") (pin "2") (pinfunction "2_2") (pintype "passive"))
      (node (ref "C29") (pin "2") (pinfunction "2_2") (pintype "passive"))
      (node (ref "C30") (pin "-") (pinfunction "-_-") (pintype "passive"))
      (node (ref "C31") (pin "-") (pinfunction "-_-") (pintype "passive"))
      (node (ref "C32") (pin "2") (pinfunction "2_2") (pintype "passive"))
      (node (ref "C33") (pin "2") (pinfunction "2_2") (pintype "passive"))
      (node (ref "C34") (pin "-") (pinfunction "-_-") (pintype "passive"))
      (node (ref "C35") (pin "-") (pinfunction "-_-") (pintype "passive"))
      (node (ref "C4") (pin "2") (pinfunction "2_2") (pintype "passive"))
      (node (ref "C5") (pin "2") (pinfunction "2_2") (pintype "passive"))
      (node (ref "C6") (pin "2") (pinfunction "2_2") (pintype "passive"))
      (node (ref "D1") (pin "1") (pinfunction "A1_1") (pintype "passive"))
      (node (ref "D2") (pin "1") (pinfunction "A1_1") (pintype "passive"))
      (node (ref "D3") (pin "1") (pinfunction "A1_1") (pintype "passive"))
      (node (ref "D4") (pin "1") (pinfunction "A1_1") (pintype "passive"))
      (node (ref "D5") (pin "1") (pinfunction "A1_1") (pintype "passive"))
      (node (ref "D6") (pin "1") (pinfunction "A1_1") (pintype "passive"))
      (node (ref "D9") (pin "K") (pinfunction "C_K") (pintype "passive"))
      (node (ref "IC1") (pin "2") (pinfunction "GND_2") (pintype "passive"))
      (node (ref "IC2") (pin "2") (pinfunction "GND_2") (pintype "passive"))
      (node (ref "J1") (pin "1@1") (pinfunction "1_1@1") (pintype "passive"))
      (node (ref "J1") (pin "1@2") (pinfunction "1_1@2") (pintype "passive"))
      (node (ref "J10") (pin "1@1") (pinfunction "1_1@1") (pintype "passive"))
      (node (ref "J10") (pin "1@2") (pinfunction "1_1@2") (pintype "passive"))
      (node (ref "J11") (pin "1@1") (pinfunction "1_1@1") (pintype "passive"))
      (node (ref "J11") (pin "1@2") (pinfunction "1_1@2") (pintype "passive"))
      (node (ref "J2") (pin "1@1") (pinfunction "1_1@1") (pintype "passive"))
      (node (ref "J2") (pin "1@2") (pinfunction "1_1@2") (pintype "passive"))
      (node (ref "J3") (pin "1@1") (pinfunction "1_1@1") (pintype "passive"))
      (node (ref "J3") (pin "1@2") (pinfunction "1_1@2") (pintype "passive"))
      (node (ref "J4") (pin "1@1") (pinfunction "1_1@1") (pintype "passive"))
      (node (ref "J4") (pin "1@2") (pinfunction "1_1@2") (pintype "passive"))
      (node (ref "J5") (pin "1@1") (pinfunction "1_1@1") (pintype "passive"))
      (node (ref "J5") (pin "1@2") (pinfunction "1_1@2") (pintype "passive"))
      (node (ref "J6") (pin "1@1") (pinfunction "1_1@1") (pintype "passive"))
      (node (ref "J6") (pin "1@2") (pinfunction "1_1@2") (pintype "passive"))
      (node (ref "J7") (pin "1@1") (pinfunction "1_1@1") (pintype "passive"))
      (node (ref "J7") (pin "1@2") (pinfunction "1_1@2") (pintype "passive"))
      (node (ref "J8") (pin "1@1") (pinfunction "1_1@1") (pintype "passive"))
      (node (ref "J8") (pin "1@2") (pinfunction "1_1@2") (pintype "passive"))
      (node (ref "J9") (pin "1@1") (pinfunction "1_1@1") (pintype "passive"))
      (node (ref "J9") (pin "1@2") (pinfunction "1_1@2") (pintype "passive"))
      (node (ref "R41") (pin "1") (pinfunction "1_1") (pintype "passive"))
      (node (ref "R42") (pin "1") (pinfunction "1_1") (pintype "passive"))
      (node (ref "R47") (pin "3") (pinfunction "A_3") (pintype "passive"))
      (node (ref "R48") (pin "1") (pinfunction "1_1") (pintype "passive"))
      (node (ref "R49") (pin "1") (pinfunction "1_1") (pintype "passive"))
      (node (ref "SV1") (pin "1") (pinfunction "1_1") (pintype "passive"))
      (node (ref "SV1") (pin "11") (pinfunction "11_11") (pintype "passive"))
      (node (ref "SV1") (pin "13") (pinfunction "13_13") (pintype "passive"))
      (node (ref "SV1") (pin "15") (pinfunction "15_15") (pintype "passive"))
      (node (ref "SV1") (pin "3") (pinfunction "3_3") (pintype "passive"))
      (node (ref "SV1") (pin "5") (pinfunction "5_5") (pintype "passive"))
      (node (ref "SV1") (pin "7") (pinfunction "7_7") (pintype "passive"))
      (node (ref "SV1") (pin "9") (pinfunction "9_9") (pintype "passive"))
      (node (ref "SV2") (pin "1") (pinfunction "1_1") (pintype "passive"))
      (node (ref "SV2") (pin "11") (pinfunction "11_11") (pintype "passive"))
      (node (ref "SV2") (pin "3") (pinfunction "3_3") (pintype "passive"))
      (node (ref "SV2") (pin "5") (pinfunction "5_5") (pintype "passive"))
      (node (ref "SV2") (pin "7") (pinfunction "7_7") (pintype "passive"))
      (node (ref "SV2") (pin "9") (pinfunction "9_9") (pintype "passive"))
      (node (ref "SV3") (pin "3") (pinfunction "3_3") (pintype "passive"))
      (node (ref "SV3") (pin "4") (pinfunction "4_4") (pintype "passive"))
      (node (ref "SV3") (pin "5") (pinfunction "5_5") (pintype "passive"))
      (node (ref "SV3") (pin "6") (pinfunction "6_6") (pintype "passive"))
      (node (ref "SV3") (pin "7") (pinfunction "7_7") (pintype "passive"))
      (node (ref "SV3") (pin "8") (pinfunction "8_8") (pintype "passive"))
      (node (ref "SV4") (pin "3") (pinfunction "3_3") (pintype "passive"))
      (node (ref "SV4") (pin "4") (pinfunction "4_4") (pintype "passive"))
      (node (ref "SV4") (pin "5") (pinfunction "5_5") (pintype "passive"))
      (node (ref "SV4") (pin "6") (pinfunction "6_6") (pintype "passive"))
      (node (ref "SV4") (pin "7") (pinfunction "7_7") (pintype "passive"))
      (node (ref "SV4") (pin "8") (pinfunction "8_8") (pintype "passive"))
      (node (ref "U1") (pin "10") (pinfunction "+IN_10") (pintype "input"))
      (node (ref "U1") (pin "12") (pinfunction "+IN_12") (pintype "input"))
      (node (ref "U1") (pin "3") (pinfunction "+IN_3") (pintype "input"))
      (node (ref "U1") (pin "5") (pinfunction "+IN_5") (pintype "input"))
      (node (ref "U2") (pin "10") (pinfunction "+IN_10") (pintype "input"))
      (node (ref "U2") (pin "12") (pinfunction "+IN_12") (pintype "input"))
      (node (ref "U2") (pin "3") (pinfunction "+IN_3") (pintype "input"))
      (node (ref "U2") (pin "5") (pinfunction "+IN_5") (pintype "input"))
      (node (ref "U3") (pin "10") (pinfunction "+IN_10") (pintype "input"))
      (node (ref "U3") (pin "12") (pinfunction "+IN_12") (pintype "input"))
      (node (ref "U3") (pin "3") (pinfunction "+IN_3") (pintype "input"))
      (node (ref "U3") (pin "5") (pinfunction "+IN_5") (pintype "input"))
      (node (ref "U4") (pin "10") (pinfunction "+IN_10") (pintype "input"))
      (node (ref "U4") (pin "12") (pinfunction "+IN_12") (pintype "input"))
      (node (ref "U4") (pin "3") (pinfunction "+IN_3") (pintype "input"))
      (node (ref "U4") (pin "5") (pinfunction "+IN_5") (pintype "input"))
      (node (ref "U5") (pin "10") (pinfunction "+IN_10") (pintype "input"))
      (node (ref "U5") (pin "12") (pinfunction "+IN_12") (pintype "input"))
      (node (ref "VR1") (pin "P$1") (pinfunction "A_P$1") (pintype "passive"))
      (node (ref "VR2") (pin "P$1") (pinfunction "A_P$1") (pintype "passive"))
      (node (ref "VR3") (pin "P$1") (pinfunction "A_P$1") (pintype "passive"))
      (node (ref "VR4") (pin "P$1") (pinfunction "A_P$1") (pintype "passive"))
      (node (ref "VR5") (pin "P$1") (pinfunction "A_P$1") (pintype "passive"))
      (node (ref "VR6") (pin "P$1") (pinfunction "A_P$1") (pintype "passive"))
      (node (ref "VR7") (pin "P$1") (pinfunction "A_P$1") (pintype "passive"))
    )
    (net (code "15") (name "INL") (class "Default")
      (node (ref "C15") (pin "1") (pinfunction "1_1") (pintype "passive"))
      (node (ref "R39") (pin "1") (pinfunction "1_1") (pintype "passive"))
      (node (ref "R42") (pin "2") (pinfunction "2_2") (pintype "passive"))
      (node (ref "R54") (pin "1") (pinfunction "1_1") (pintype "passive"))
      (node (ref "SV2") (pin "2") (pinfunction "2_2") (pintype "passive"))
    )
    (net (code "16") (name "INR") (class "Default")
      (node (ref "C14") (pin "1") (pinfunction "1_1") (pintype "passive"))
      (node (ref "R38") (pin "1") (pinfunction "1_1") (pintype "passive"))
      (node (ref "R41") (pin "2") (pinfunction "2_2") (pintype "passive"))
      (node (ref "R55") (pin "1") (pinfunction "1_1") (pintype "passive"))
      (node (ref "SV2") (pin "4") (pinfunction "4_4") (pintype "passive"))
    )
    (net (code "17") (name "Net-(D9-PadA)") (class "Default")
      (node (ref "D9") (pin "A") (pinfunction "A_A") (pintype "passive"))
      (node (ref "R43") (pin "2") (pinfunction "2_2") (pintype "passive"))
    )
    (net (code "18") (name "Net-(J7-Pad2)") (class "Default")
      (node (ref "J7") (pin "2") (pinfunction "2_2") (pintype "passive"))
      (node (ref "J8") (pin "3") (pinfunction "3_3") (pintype "passive"))
      (node (ref "R32") (pin "2") (pinfunction "2_2") (pintype "passive"))
    )
    (net (code "19") (name "Net-(J7-Pad3)") (class "Default")
      (node (ref "J7") (pin "3") (pinfunction "3_3") (pintype "passive"))
      (node (ref "R31") (pin "2") (pinfunction "2_2") (pintype "passive"))
    )
    (net (code "20") (name "Net-(Q1-B)") (class "Default")
      (node (ref "Q1") (pin "2") (pinfunction "B_2") (pintype "passive"))
      (node (ref "R44") (pin "2") (pinfunction "2_2") (pintype "passive"))
    )
    (net (code "21") (name "Net-(Q1-C)") (class "Default")
      (node (ref "Q1") (pin "1") (pinfunction "C_1") (pintype "passive"))
      (node (ref "R45") (pin "1") (pinfunction "1_1") (pintype "passive"))
    )
    (net (code "22") (name "Net-(Q1-E)") (class "Default")
      (node (ref "Q1") (pin "3") (pinfunction "E_3") (pintype "passive"))
      (node (ref "R46") (pin "1") (pinfunction "1_1") (pintype "passive"))
    )
    (net (code "23") (name "Net-(R47-E)") (class "Default")
      (node (ref "R46") (pin "2") (pinfunction "2_2") (pintype "passive"))
      (node (ref "R47") (pin "1") (pinfunction "E_1") (pintype "passive"))
      (node (ref "R47") (pin "2") (pinfunction "S_2") (pintype "passive"))
    )
    (net (code "24") (name "Net-(U1A--IN)") (class "Default")
      (node (ref "C1") (pin "1") (pinfunction "1_1") (pintype "passive"))
      (node (ref "R10") (pin "1") (pinfunction "1_1") (pintype "passive"))
      (node (ref "R7") (pin "2") (pinfunction "2_2") (pintype "passive"))
      (node (ref "U1") (pin "2") (pinfunction "-IN_2") (pintype "input"))
    )
    (net (code "25") (name "Net-(U1A-OUT)") (class "Default")
      (node (ref "C1") (pin "2") (pinfunction "2_2") (pintype "passive"))
      (node (ref "R10") (pin "2") (pinfunction "2_2") (pintype "passive"))
      (node (ref "R13") (pin "1") (pinfunction "1_1") (pintype "passive"))
      (node (ref "U1") (pin "1") (pinfunction "OUT_1") (pintype "output"))
    )
    (net (code "26") (name "Net-(U1B--IN)") (class "Default")
      (node (ref "R1") (pin "2") (pinfunction "2_2") (pintype "passive"))
      (node (ref "R4") (pin "1") (pinfunction "1_1") (pintype "passive"))
      (node (ref "U1") (pin "6") (pinfunction "-IN_6") (pintype "input"))
    )
    (net (code "27") (name "Net-(U1B-OUT)") (class "Default")
      (node (ref "R4") (pin "2") (pinfunction "2_2") (pintype "passive"))
      (node (ref "R7") (pin "1") (pinfunction "1_1") (pintype "passive"))
      (node (ref "U1") (pin "7") (pinfunction "OUT_7") (pintype "output"))
    )
    (net (code "28") (name "Net-(U1C--IN)") (class "Default")
      (node (ref "R2") (pin "2") (pinfunction "2_2") (pintype "passive"))
      (node (ref "R5") (pin "1") (pinfunction "1_1") (pintype "passive"))
      (node (ref "U1") (pin "9") (pinfunction "-IN_9") (pintype "input"))
    )
    (net (code "29") (name "Net-(U1C-OUT)") (class "Default")
      (node (ref "R5") (pin "2") (pinfunction "2_2") (pintype "passive"))
      (node (ref "R8") (pin "1") (pinfunction "1_1") (pintype "passive"))
      (node (ref "U1") (pin "8") (pinfunction "OUT_8") (pintype "output"))
    )
    (net (code "30") (name "Net-(U1D--IN)") (class "Default")
      (node (ref "C2") (pin "1") (pinfunction "1_1") (pintype "passive"))
      (node (ref "R11") (pin "1") (pinfunction "1_1") (pintype "passive"))
      (node (ref "R8") (pin "2") (pinfunction "2_2") (pintype "passive"))
      (node (ref "U1") (pin "13") (pinfunction "-IN_13") (pintype "input"))
    )
    (net (code "31") (name "Net-(U1D-OUT)") (class "Default")
      (node (ref "C2") (pin "2") (pinfunction "2_2") (pintype "passive"))
      (node (ref "R11") (pin "2") (pinfunction "2_2") (pintype "passive"))
      (node (ref "R14") (pin "1") (pinfunction "1_1") (pintype "passive"))
      (node (ref "U1") (pin "14") (pinfunction "OUT_14") (pintype "output"))
    )
    (net (code "32") (name "Net-(U2A--IN)") (class "Default")
      (node (ref "C3") (pin "1") (pinfunction "1_1") (pintype "passive"))
      (node (ref "R12") (pin "1") (pinfunction "1_1") (pintype "passive"))
      (node (ref "R9") (pin "2") (pinfunction "2_2") (pintype "passive"))
      (node (ref "U2") (pin "2") (pinfunction "-IN_2") (pintype "input"))
    )
    (net (code "33") (name "Net-(U2A-OUT)") (class "Default")
      (node (ref "C3") (pin "2") (pinfunction "2_2") (pintype "passive"))
      (node (ref "R12") (pin "2") (pinfunction "2_2") (pintype "passive"))
      (node (ref "R15") (pin "1") (pinfunction "1_1") (pintype "passive"))
      (node (ref "U2") (pin "1") (pinfunction "OUT_1") (pintype "output"))
    )
    (net (code "34") (name "Net-(U2B--IN)") (class "Default")
      (node (ref "R3") (pin "2") (pinfunction "2_2") (pintype "passive"))
      (node (ref "R6") (pin "1") (pinfunction "1_1") (pintype "passive"))
      (node (ref "U2") (pin "6") (pinfunction "-IN_6") (pintype "input"))
    )
    (net (code "35") (name "Net-(U2B-OUT)") (class "Default")
      (node (ref "R6") (pin "2") (pinfunction "2_2") (pintype "passive"))
      (node (ref "R9") (pin "1") (pinfunction "1_1") (pintype "passive"))
      (node (ref "U2") (pin "7") (pinfunction "OUT_7") (pintype "output"))
    )
    (net (code "36") (name "Net-(U2C--IN)") (class "Default")
      (node (ref "R16") (pin "2") (pinfunction "2_2") (pintype "passive"))
      (node (ref "R19") (pin "1") (pinfunction "1_1") (pintype "passive"))
      (node (ref "U2") (pin "9") (pinfunction "-IN_9") (pintype "input"))
    )
    (net (code "37") (name "Net-(U2C-OUT)") (class "Default")
      (node (ref "R19") (pin "2") (pinfunction "2_2") (pintype "passive"))
      (node (ref "R22") (pin "1") (pinfunction "1_1") (pintype "passive"))
      (node (ref "U2") (pin "8") (pinfunction "OUT_8") (pintype "output"))
    )
    (net (code "38") (name "Net-(U2D--IN)") (class "Default")
      (node (ref "C7") (pin "1") (pinfunction "1_1") (pintype "passive"))
      (node (ref "R22") (pin "2") (pinfunction "2_2") (pintype "passive"))
      (node (ref "R25") (pin "1") (pinfunction "1_1") (pintype "passive"))
      (node (ref "U2") (pin "13") (pinfunction "-IN_13") (pintype "input"))
    )
    (net (code "39") (name "Net-(U2D-OUT)") (class "Default")
      (node (ref "C7") (pin "2") (pinfunction "2_2") (pintype "passive"))
      (node (ref "R25") (pin "2") (pinfunction "2_2") (pintype "passive"))
      (node (ref "R28") (pin "1") (pinfunction "1_1") (pintype "passive"))
      (node (ref "U2") (pin "14") (pinfunction "OUT_14") (pintype "output"))
    )
    (net (code "40") (name "Net-(U3A--IN)") (class "Default")
      (node (ref "C8") (pin "1") (pinfunction "1_1") (pintype "passive"))
      (node (ref "R23") (pin "2") (pinfunction "2_2") (pintype "passive"))
      (node (ref "R26") (pin "1") (pinfunction "1_1") (pintype "passive"))
      (node (ref "U3") (pin "2") (pinfunction "-IN_2") (pintype "input"))
    )
    (net (code "41") (name "Net-(U3A-OUT)") (class "Default")
      (node (ref "C8") (pin "2") (pinfunction "2_2") (pintype "passive"))
      (node (ref "R26") (pin "2") (pinfunction "2_2") (pintype "passive"))
      (node (ref "R29") (pin "1") (pinfunction "1_1") (pintype "passive"))
      (node (ref "U3") (pin "1") (pinfunction "OUT_1") (pintype "output"))
    )
    (net (code "42") (name "Net-(U3B--IN)") (class "Default")
      (node (ref "R17") (pin "2") (pinfunction "2_2") (pintype "passive"))
      (node (ref "R20") (pin "1") (pinfunction "1_1") (pintype "passive"))
      (node (ref "U3") (pin "6") (pinfunction "-IN_6") (pintype "input"))
    )
    (net (code "43") (name "Net-(U3B-OUT)") (class "Default")
      (node (ref "R20") (pin "2") (pinfunction "2_2") (pintype "passive"))
      (node (ref "R23") (pin "1") (pinfunction "1_1") (pintype "passive"))
      (node (ref "U3") (pin "7") (pinfunction "OUT_7") (pintype "output"))
    )
    (net (code "44") (name "Net-(U3C--IN)") (class "Default")
      (node (ref "R18") (pin "2") (pinfunction "2_2") (pintype "passive"))
      (node (ref "R21") (pin "1") (pinfunction "1_1") (pintype "passive"))
      (node (ref "U3") (pin "9") (pinfunction "-IN_9") (pintype "input"))
    )
    (net (code "45") (name "Net-(U3C-OUT)") (class "Default")
      (node (ref "R21") (pin "2") (pinfunction "2_2") (pintype "passive"))
      (node (ref "R24") (pin "1") (pinfunction "1_1") (pintype "passive"))
      (node (ref "U3") (pin "8") (pinfunction "OUT_8") (pintype "output"))
    )
    (net (code "46") (name "Net-(U3D--IN)") (class "Default")
      (node (ref "C9") (pin "1") (pinfunction "1_1") (pintype "passive"))
      (node (ref "R24") (pin "2") (pinfunction "2_2") (pintype "passive"))
      (node (ref "R27") (pin "1") (pinfunction "1_1") (pintype "passive"))
      (node (ref "U3") (pin "13") (pinfunction "-IN_13") (pintype "input"))
    )
    (net (code "47") (name "Net-(U3D-OUT)") (class "Default")
      (node (ref "C9") (pin "2") (pinfunction "2_2") (pintype "passive"))
      (node (ref "R27") (pin "2") (pinfunction "2_2") (pintype "passive"))
      (node (ref "R30") (pin "1") (pinfunction "1_1") (pintype "passive"))
      (node (ref "U3") (pin "14") (pinfunction "OUT_14") (pintype "output"))
    )
    (net (code "48") (name "Net-(U4A--IN)") (class "Default")
      (node (ref "R31") (pin "1") (pinfunction "1_1") (pintype "passive"))
      (node (ref "R34") (pin "2") (pinfunction "2_2") (pintype "passive"))
      (node (ref "U4") (pin "2") (pinfunction "-IN_2") (pintype "input"))
    )
    (net (code "49") (name "Net-(U4A-OUT)") (class "Default")
      (node (ref "R38") (pin "2") (pinfunction "2_2") (pintype "passive"))
      (node (ref "U4") (pin "1") (pinfunction "OUT_1") (pintype "output"))
      (node (ref "VR8") (pin "A2") (pinfunction "S_A2") (pintype "passive"))
      (node (ref "VR8") (pin "A3") (pinfunction "E_A3") (pintype "passive"))
    )
    (net (code "50") (name "Net-(U4B--IN)") (class "Default")
      (node (ref "R32") (pin "1") (pinfunction "1_1") (pintype "passive"))
      (node (ref "R35") (pin "2") (pinfunction "2_2") (pintype "passive"))
      (node (ref "U4") (pin "6") (pinfunction "-IN_6") (pintype "input"))
    )
    (net (code "51") (name "Net-(U4B-OUT)") (class "Default")
      (node (ref "R39") (pin "2") (pinfunction "2_2") (pintype "passive"))
      (node (ref "U4") (pin "7") (pinfunction "OUT_7") (pintype "output"))
      (node (ref "VR8") (pin "B2") (pinfunction "S_B2") (pintype "passive"))
      (node (ref "VR8") (pin "B3") (pinfunction "E_B3") (pintype "passive"))
    )
    (net (code "52") (name "Net-(U4C--IN)") (class "Default")
      (node (ref "C16") (pin "1") (pinfunction "1_1") (pintype "passive"))
      (node (ref "R50") (pin "1") (pinfunction "1_1") (pintype "passive"))
      (node (ref "R52") (pin "2") (pinfunction "2_2") (pintype "passive"))
      (node (ref "U4") (pin "9") (pinfunction "-IN_9") (pintype "input"))
    )
    (net (code "53") (name "Net-(U4C-OUT)") (class "Default")
      (node (ref "C16") (pin "2") (pinfunction "2_2") (pintype "passive"))
      (node (ref "R52") (pin "1") (pinfunction "1_1") (pintype "passive"))
      (node (ref "R56") (pin "2") (pinfunction "2_2") (pintype "passive"))
      (node (ref "U4") (pin "8") (pinfunction "OUT_8") (pintype "output"))
    )
    (net (code "54") (name "Net-(U4D--IN)") (class "Default")
      (node (ref "C17") (pin "1") (pinfunction "1_1") (pintype "passive"))
      (node (ref "R51") (pin "1") (pinfunction "1_1") (pintype "passive"))
      (node (ref "R53") (pin "2") (pinfunction "2_2") (pintype "passive"))
      (node (ref "U4") (pin "13") (pinfunction "-IN_13") (pintype "input"))
    )
    (net (code "55") (name "Net-(U4D-OUT)") (class "Default")
      (node (ref "C17") (pin "2") (pinfunction "2_2") (pintype "passive"))
      (node (ref "R53") (pin "1") (pinfunction "1_1") (pintype "passive"))
      (node (ref "R57") (pin "2") (pinfunction "2_2") (pintype "passive"))
      (node (ref "U4") (pin "14") (pinfunction "OUT_14") (pintype "output"))
    )
    (net (code "56") (name "Net-(U5A-+IN)") (class "Default")
      (node (ref "C19") (pin "1") (pinfunction "1_1") (pintype "passive"))
      (node (ref "R55") (pin "2") (pinfunction "2_2") (pintype "passive"))
      (node (ref "U5") (pin "3") (pinfunction "+IN_3") (pintype "input"))
      (node (ref "V2") (pin "4") (pinfunction "RES2_4") (pintype "passive"))
    )
    (net (code "57") (name "Net-(U5A--IN)") (class "Default")
      (node (ref "J11") (pin "3") (pinfunction "3_3") (pintype "passive"))
      (node (ref "R59") (pin "2") (pinfunction "2_2") (pintype "passive"))
      (node (ref "U5") (pin "2") (pinfunction "-IN_2") (pintype "input"))
    )
    (net (code "58") (name "Net-(U5A-OUT)") (class "Default")
      (node (ref "R59") (pin "1") (pinfunction "1_1") (pintype "passive"))
      (node (ref "U5") (pin "1") (pinfunction "OUT_1") (pintype "output"))
    )
    (net (code "59") (name "Net-(U5B-+IN)") (class "Default")
      (node (ref "C18") (pin "1") (pinfunction "1_1") (pintype "passive"))
      (node (ref "R54") (pin "2") (pinfunction "2_2") (pintype "passive"))
      (node (ref "U5") (pin "5") (pinfunction "+IN_5") (pintype "input"))
      (node (ref "V1") (pin "4") (pinfunction "RES2_4") (pintype "passive"))
    )
    (net (code "60") (name "Net-(U5B--IN)") (class "Default")
      (node (ref "J10") (pin "3") (pinfunction "3_3") (pintype "passive"))
      (node (ref "R58") (pin "2") (pinfunction "2_2") (pintype "passive"))
      (node (ref "U5") (pin "6") (pinfunction "-IN_6") (pintype "input"))
    )
    (net (code "61") (name "Net-(U5B-OUT)") (class "Default")
      (node (ref "R58") (pin "1") (pinfunction "1_1") (pintype "passive"))
      (node (ref "U5") (pin "7") (pinfunction "OUT_7") (pintype "output"))
    )
    (net (code "62") (name "Net-(U5C--IN)") (class "Default")
      (node (ref "C13") (pin "1") (pinfunction "1_1") (pintype "passive"))
      (node (ref "R37") (pin "2") (pinfunction "2_2") (pintype "passive"))
      (node (ref "R40") (pin "1") (pinfunction "1_1") (pintype "passive"))
      (node (ref "U5") (pin "9") (pinfunction "-IN_9") (pintype "input"))
    )
    (net (code "63") (name "Net-(U5C-OUT)") (class "Default")
      (node (ref "C13") (pin "2") (pinfunction "2_2") (pintype "passive"))
      (node (ref "R40") (pin "2") (pinfunction "2_2") (pintype "passive"))
      (node (ref "R43") (pin "1") (pinfunction "1_1") (pintype "passive"))
      (node (ref "R44") (pin "1") (pinfunction "1_1") (pintype "passive"))
      (node (ref "U5") (pin "8") (pinfunction "OUT_8") (pintype "output"))
    )
    (net (code "64") (name "Net-(U5D--IN)") (class "Default")
      (node (ref "R33") (pin "2") (pinfunction "2_2") (pintype "passive"))
      (node (ref "R36") (pin "1") (pinfunction "1_1") (pintype "passive"))
      (node (ref "U5") (pin "13") (pinfunction "-IN_13") (pintype "input"))
    )
    (net (code "65") (name "Net-(U5D-OUT)") (class "Default")
      (node (ref "R36") (pin "2") (pinfunction "2_2") (pintype "passive"))
      (node (ref "R37") (pin "1") (pinfunction "1_1") (pintype "passive"))
      (node (ref "U5") (pin "14") (pinfunction "OUT_14") (pintype "output"))
    )
    (net (code "66") (name "Net-(VR1-E)") (class "Default")
      (node (ref "J1") (pin "3") (pinfunction "3_3") (pintype "passive"))
      (node (ref "VR1") (pin "P$3") (pinfunction "E_P$3") (pintype "passive"))
    )
    (net (code "67") (name "Net-(VR1-S)") (class "Default")
      (node (ref "R1") (pin "1") (pinfunction "1_1") (pintype "passive"))
      (node (ref "VR1") (pin "P$2") (pinfunction "S_P$2") (pintype "passive"))
    )
    (net (code "68") (name "Net-(VR2-E)") (class "Default")
      (node (ref "J2") (pin "3") (pinfunction "3_3") (pintype "passive"))
      (node (ref "VR2") (pin "P$3") (pinfunction "E_P$3") (pintype "passive"))
    )
    (net (code "69") (name "Net-(VR2-S)") (class "Default")
      (node (ref "R2") (pin "1") (pinfunction "1_1") (pintype "passive"))
      (node (ref "VR2") (pin "P$2") (pinfunction "S_P$2") (pintype "passive"))
    )
    (net (code "70") (name "Net-(VR3-E)") (class "Default")
      (node (ref "J3") (pin "3") (pinfunction "3_3") (pintype "passive"))
      (node (ref "VR3") (pin "P$3") (pinfunction "E_P$3") (pintype "passive"))
    )
    (net (code "71") (name "Net-(VR3-S)") (class "Default")
      (node (ref "R3") (pin "1") (pinfunction "1_1") (pintype "passive"))
      (node (ref "VR3") (pin "P$2") (pinfunction "S_P$2") (pintype "passive"))
    )
    (net (code "72") (name "Net-(VR4-E)") (class "Default")
      (node (ref "J4") (pin "3") (pinfunction "3_3") (pintype "passive"))
      (node (ref "VR4") (pin "P$3") (pinfunction "E_P$3") (pintype "passive"))
    )
    (net (code "73") (name "Net-(VR4-S)") (class "Default")
      (node (ref "R16") (pin "1") (pinfunction "1_1") (pintype "passive"))
      (node (ref "VR4") (pin "P$2") (pinfunction "S_P$2") (pintype "passive"))
    )
    (net (code "74") (name "Net-(VR5-E)") (class "Default")
      (node (ref "J5") (pin "3") (pinfunction "3_3") (pintype "passive"))
      (node (ref "VR5") (pin "P$3") (pinfunction "E_P$3") (pintype "passive"))
    )
    (net (code "75") (name "Net-(VR5-S)") (class "Default")
      (node (ref "R17") (pin "1") (pinfunction "1_1") (pintype "passive"))
      (node (ref "VR5") (pin "P$2") (pinfunction "S_P$2") (pintype "passive"))
    )
    (net (code "76") (name "Net-(VR6-E)") (class "Default")
      (node (ref "J6") (pin "3") (pinfunction "3_3") (pintype "passive"))
      (node (ref "VR6") (pin "P$3") (pinfunction "E_P$3") (pintype "passive"))
    )
    (net (code "77") (name "Net-(VR6-S)") (class "Default")
      (node (ref "R18") (pin "1") (pinfunction "1_1") (pintype "passive"))
      (node (ref "VR6") (pin "P$2") (pinfunction "S_P$2") (pintype "passive"))
    )
    (net (code "78") (name "Net-(VR7-E)") (class "Default")
      (node (ref "J9") (pin "3") (pinfunction "3_3") (pintype "passive"))
      (node (ref "VR7") (pin "P$3") (pinfunction "E_P$3") (pintype "passive"))
    )
    (net (code "79") (name "Net-(VR7-S)") (class "Default")
      (node (ref "R33") (pin "1") (pinfunction "1_1") (pintype "passive"))
      (node (ref "VR7") (pin "P$2") (pinfunction "S_P$2") (pintype "passive"))
    )
    (net (code "80") (name "Net-(VR8A-A)") (class "Default")
      (node (ref "R34") (pin "1") (pinfunction "1_1") (pintype "passive"))
      (node (ref "VR8") (pin "A1") (pinfunction "A_A1") (pintype "passive"))
    )
    (net (code "81") (name "Net-(VR8B-A)") (class "Default")
      (node (ref "R35") (pin "1") (pinfunction "1_1") (pintype "passive"))
      (node (ref "VR8") (pin "B1") (pinfunction "A_B1") (pintype "passive"))
    )
    (net (code "82") (name "OUTL") (class "Default")
      (node (ref "R49") (pin "2") (pinfunction "2_2") (pintype "passive"))
      (node (ref "R51") (pin "2") (pinfunction "2_2") (pintype "passive"))
      (node (ref "SV2") (pin "10") (pinfunction "10_10") (pintype "passive"))
    )
    (net (code "83") (name "OUTR") (class "Default")
      (node (ref "R48") (pin "2") (pinfunction "2_2") (pintype "passive"))
      (node (ref "R50") (pin "2") (pinfunction "2_2") (pintype "passive"))
      (node (ref "SV2") (pin "12") (pinfunction "12_12") (pintype "passive"))
    )
    (net (code "84") (name "VDD") (class "Default")
      (node (ref "D7") (pin "A") (pinfunction "A_A") (pintype "passive"))
      (node (ref "SV3") (pin "10") (pinfunction "10_10") (pintype "passive"))
      (node (ref "SV3") (pin "9") (pinfunction "9_9") (pintype "passive"))
    )
    (net (code "85") (name "VSS") (class "Default")
      (node (ref "D8") (pin "C") (pinfunction "C_C") (pintype "passive"))
      (node (ref "SV3") (pin "1") (pinfunction "1_1") (pintype "passive"))
      (node (ref "SV3") (pin "2") (pinfunction "2_2") (pintype "passive"))
    )
    (net (code "86") (name "WET_L") (class "Default")
      (node (ref "R57") (pin "1") (pinfunction "1_1") (pintype "passive"))
      (node (ref "V1") (pin "3") (pinfunction "RES1_3") (pintype "passive"))
    )
    (net (code "87") (name "WET_R") (class "Default")
      (node (ref "R56") (pin "1") (pinfunction "1_1") (pintype "passive"))
      (node (ref "V2") (pin "3") (pinfunction "RES1_3") (pintype "passive"))
    )
    (net (code "88") (name "unconnected-(J8-Pad2)") (class "Default")
      (node (ref "J8") (pin "2") (pinfunction "2_2") (pintype "passive"))
    )
    (net (code "89") (name "unconnected-(J10-Pad2)") (class "Default")
      (node (ref "J10") (pin "2") (pinfunction "2_2") (pintype "passive"))
    )
    (net (code "90") (name "unconnected-(J11-Pad2)") (class "Default")
      (node (ref "J11") (pin "2") (pinfunction "2_2") (pintype "passive"))
    )
    (net (code "91") (name "unconnected-(SV2-Pad6)") (class "Default")
      (node (ref "SV2") (pin "6") (pinfunction "6_6") (pintype "passive"))
    )
    (net (code "92") (name "unconnected-(SV2-Pad8)") (class "Default")
      (node (ref "SV2") (pin "8") (pinfunction "8_8") (pintype "passive"))
    )
  )
)
